# TestHBridge.net
KiCad netlist of a schematic drawn in Altium Designer
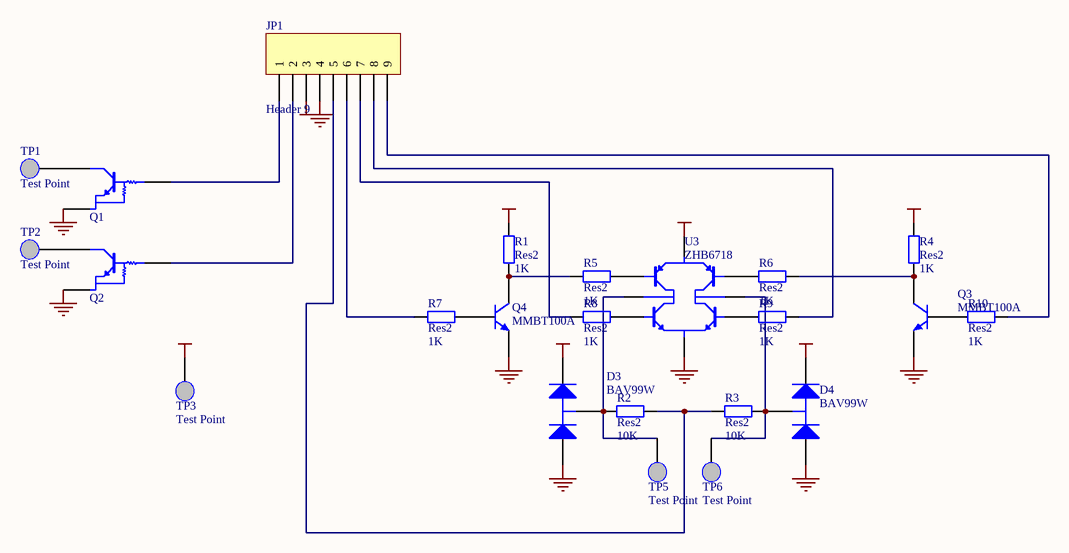
[diagram p0: TestHBridge.SchDoc]

(export (version "E")
  (design (tool "Eeschema 10.0.6"))
  (components
    (comp (ref "D3")
      (value "BAV99W")
      (footprint "SOT-323")
      (description "Silicon Switching Diode Array for High-Speed Switching")
      (fields (field (name "PUBLISHER") "Altium Limited"))
      (libsource (lib "Infineon Discrete Diode") (part "BAV99W"))
    )
    (comp (ref "D4")
      (value "BAV99W")
      (footprint "SOT-323")
      (description "Silicon Switching Diode Array for High-Speed Switching")
      (fields (field (name "PUBLISHER") "Altium Limited"))
      (libsource (lib "Infineon Discrete Diode") (part "BAV99W"))
    )
    (comp (ref "JP1")
      (value "Header 9")
      (footprint "HDR1X9")
      (description "Header, 9-Pin")
      (fields (field (name "PUBLISHER") "Altium Limited"))
      (libsource (lib "Miscellaneous Connectors") (part "Header 9"))
    )
    (comp (ref "Q1")
      (value "UN2212")
      (footprint "SO-G3")
      (description "Bias Resistor Transistor")
      (libsource (lib "Custom") (part "UN2212"))
    )
    (comp (ref "Q2")
      (value "UN2212")
      (footprint "SO-G3")
      (description "Bias Resistor Transistor")
      (libsource (lib "Custom") (part "UN2212"))
    )
    (comp (ref "Q3")
      (value "MMBT100A")
      (footprint "SO-G3")
      (description "General Purpose Amplifier NPN Silicon")
      (fields (field (name "PUBLISHER") "Altium Limited"))
      (libsource (lib "Custom") (part "MMBT100A"))
    )
    (comp (ref "Q4")
      (value "MMBT100A")
      (footprint "SO-G3")
      (description "General Purpose Amplifier NPN Silicon")
      (fields (field (name "PUBLISHER") "Altium Limited"))
      (libsource (lib "Custom") (part "MMBT100A"))
    )
    (comp (ref "R1")
      (value "Res2")
      (footprint "CC2012-0805")
      (description "Resistor")
      (fields (field (name "ALTIUM_VALUE") "1K") (field (name "PUBLISHER") "Altium Limited"))
      (libsource (lib "Miscellaneous Devices") (part "Res2"))
    )
    (comp (ref "R2")
      (value "Res2")
      (footprint "CC2012-0805")
      (description "Resistor")
      (fields (field (name "ALTIUM_VALUE") "10K") (field (name "PUBLISHER") "Altium Limited"))
      (libsource (lib "Miscellaneous Devices") (part "Res2"))
    )
    (comp (ref "R3")
      (value "Res2")
      (footprint "CC2012-0805")
      (description "Resistor")
      (fields (field (name "ALTIUM_VALUE") "10K") (field (name "PUBLISHER") "Altium Limited"))
      (libsource (lib "Miscellaneous Devices") (part "Res2"))
    )
    (comp (ref "R4")
      (value "Res2")
      (footprint "CC2012-0805")
      (description "Resistor")
      (fields (field (name "ALTIUM_VALUE") "1K") (field (name "PUBLISHER") "Altium Limited"))
      (libsource (lib "") (part "Res2_2"))
    )
    (comp (ref "R5")
      (value "Res2")
      (footprint "CC2012-0805")
      (description "Resistor")
      (fields (field (name "ALTIUM_VALUE") "1K") (field (name "PUBLISHER") "Altium Limited"))
      (libsource (lib "Miscellaneous Devices") (part "Res2"))
    )
    (comp (ref "R6")
      (value "Res2")
      (footprint "CC2012-0805")
      (description "Resistor")
      (fields (field (name "ALTIUM_VALUE") "1K") (field (name "PUBLISHER") "Altium Limited"))
      (libsource (lib "Miscellaneous Devices") (part "Res2"))
    )
    (comp (ref "R7")
      (value "Res2")
      (footprint "CC2012-0805")
      (description "Resistor")
      (fields (field (name "ALTIUM_VALUE") "1K") (field (name "PUBLISHER") "Altium Limited"))
      (libsource (lib "") (part "Res2_1"))
    )
    (comp (ref "R8")
      (value "Res2")
      (footprint "CC2012-0805")
      (description "Resistor")
      (fields (field (name "ALTIUM_VALUE") "1K") (field (name "PUBLISHER") "Altium Limited"))
      (libsource (lib "Miscellaneous Devices") (part "Res2"))
    )
    (comp (ref "R9")
      (value "Res2")
      (footprint "CC2012-0805")
      (description "Resistor")
      (fields (field (name "ALTIUM_VALUE") "1K") (field (name "PUBLISHER") "Altium Limited"))
      (libsource (lib "Miscellaneous Devices") (part "Res2"))
    )
    (comp (ref "R10")
      (value "Res2")
      (footprint "CC2012-0805")
      (description "Resistor")
      (fields (field (name "ALTIUM_VALUE") "1K") (field (name "PUBLISHER") "Altium Limited"))
      (libsource (lib "Miscellaneous Devices") (part "Res2"))
    )
    (comp (ref "TP1")
      (value "Test Point")
      (footprint "TestPoint")
      (libsource (lib "Custom") (part "TestPoint"))
    )
    (comp (ref "TP2")
      (value "Test Point")
      (footprint "TestPoint")
      (libsource (lib "Custom") (part "TestPoint"))
    )
    (comp (ref "TP3")
      (value "Test Point")
      (footprint "TestPoint")
      (libsource (lib "Custom") (part "TestPoint"))
    )
    (comp (ref "TP5")
      (value "Test Point")
      (footprint "TestPoint")
      (libsource (lib "Custom") (part "TestPoint"))
    )
    (comp (ref "TP6")
      (value "Test Point")
      (footprint "TestPoint")
      (libsource (lib "Custom") (part "TestPoint"))
    )
    (comp (ref "U3") (value "ZHB6718") (footprint "SOT223-8") (libsource (lib "Custom") (part "ZHB6718")))
  )
  (nets
    (net (code "1") (name "GND") (class "Default")
      (node (ref "D3") (pin "1") (pinfunction "A_1") (pintype "passive"))
      (node (ref "D4") (pin "1") (pinfunction "A_1") (pintype "passive"))
      (node (ref "JP1") (pin "4") (pinfunction "4_4") (pintype "passive"))
      (node (ref "Q1") (pin "2") (pinfunction "E_2") (pintype "passive"))
      (node (ref "Q2") (pin "2") (pinfunction "E_2") (pintype "passive"))
      (node (ref "Q3") (pin "2") (pinfunction "E_2") (pintype "passive"))
      (node (ref "Q4") (pin "2") (pinfunction "E_2") (pintype "passive"))
      (node (ref "U3") (pin "2") (pinfunction "e2,e3_2") (pintype "passive"))
    )
    (net (code "2") (name "Net-(D3-C)") (class "Default")
      (node (ref "D3") (pin "3") (pinfunction "C_3") (pintype "passive"))
      (node (ref "R2") (pin "1") (pinfunction "1_1") (pintype "passive"))
      (node (ref "TP5") (pin "1") (pintype "passive"))
      (node (ref "U3") (pin "5") (pinfunction "c1,c2_5") (pintype "passive"))
    )
    (net (code "3") (name "Net-(D4-C)") (class "Default")
      (node (ref "D4") (pin "3") (pinfunction "C_3") (pintype "passive"))
      (node (ref "R3") (pin "2") (pinfunction "2_2") (pintype "passive"))
      (node (ref "TP6") (pin "1") (pintype "passive"))
      (node (ref "U3") (pin "7") (pinfunction "c3,c4_7") (pintype "passive"))
    )
    (net (code "4") (name "Net-(JP1-Pad5)") (class "Default")
      (node (ref "JP1") (pin "5") (pinfunction "5_5") (pintype "passive"))
      (node (ref "R2") (pin "2") (pinfunction "2_2") (pintype "passive"))
      (node (ref "R3") (pin "1") (pinfunction "1_1") (pintype "passive"))
    )
    (net (code "5") (name "Net-(JP1-Pad6)") (class "Default")
      (node (ref "JP1") (pin "6") (pinfunction "6_6") (pintype "passive"))
      (node (ref "R7") (pin "2") (pinfunction "2_2") (pintype "passive"))
    )
    (net (code "6") (name "Net-(JP1-Pad7)") (class "Default")
      (node (ref "JP1") (pin "7") (pinfunction "7_7") (pintype "passive"))
      (node (ref "R8") (pin "1") (pinfunction "1_1") (pintype "passive"))
    )
    (net (code "7") (name "Net-(JP1-Pad8)") (class "Default")
      (node (ref "JP1") (pin "8") (pinfunction "8_8") (pintype "passive"))
      (node (ref "R9") (pin "2") (pinfunction "2_2") (pintype "passive"))
    )
    (net (code "8") (name "Net-(JP1-Pad9)") (class "Default")
      (node (ref "JP1") (pin "9") (pinfunction "9_9") (pintype "passive"))
      (node (ref "R10") (pin "2") (pinfunction "2_2") (pintype "passive"))
    )
    (net (code "9") (name "Net-(Q1-B)") (class "Default")
      (node (ref "JP1") (pin "1") (pinfunction "1_1") (pintype "passive"))
      (node (ref "Q1") (pin "1") (pinfunction "B_1") (pintype "passive"))
    )
    (net (code "10") (name "Net-(Q1-C)") (class "Default")
      (node (ref "Q1") (pin "3") (pinfunction "C_3") (pintype "passive"))
      (node (ref "TP1") (pin "1") (pintype "passive"))
    )
    (net (code "11") (name "Net-(Q2-B)") (class "Default")
      (node (ref "JP1") (pin "2") (pinfunction "2_2") (pintype "passive"))
      (node (ref "Q2") (pin "1") (pinfunction "B_1") (pintype "passive"))
    )
    (net (code "12") (name "Net-(Q2-C)") (class "Default")
      (node (ref "Q2") (pin "3") (pinfunction "C_3") (pintype "passive"))
      (node (ref "TP2") (pin "1") (pintype "passive"))
    )
    (net (code "13") (name "Net-(Q3-B)") (class "Default")
      (node (ref "Q3") (pin "1") (pinfunction "B_1") (pintype "passive"))
      (node (ref "R10") (pin "1") (pinfunction "1_1") (pintype "passive"))
    )
    (net (code "14") (name "Net-(Q3-C)") (class "Default")
      (node (ref "Q3") (pin "3") (pinfunction "C_3") (pintype "passive"))
      (node (ref "R4") (pin "1") (pinfunction "1_1") (pintype "passive"))
      (node (ref "R6") (pin "2") (pinfunction "2_2") (pintype "passive"))
    )
    (net (code "15") (name "Net-(Q4-B)") (class "Default")
      (node (ref "Q4") (pin "1") (pinfunction "B_1") (pintype "passive"))
      (node (ref "R7") (pin "1") (pinfunction "1_1") (pintype "passive"))
    )
    (net (code "16") (name "Net-(Q4-C)") (class "Default")
      (node (ref "Q4") (pin "3") (pinfunction "C_3") (pintype "passive"))
      (node (ref "R1") (pin "1") (pinfunction "1_1") (pintype "passive"))
      (node (ref "R5") (pin "1") (pinfunction "1_1") (pintype "passive"))
    )
    (net (code "17") (name "Net-(U3-b1)") (class "Default")
      (node (ref "R5") (pin "2") (pinfunction "2_2") (pintype "passive"))
      (node (ref "U3") (pin "4") (pinfunction "b1_4") (pintype "passive"))
    )
    (net (code "18") (name "Net-(U3-b2)") (class "Default")
      (node (ref "R8") (pin "2") (pinfunction "2_2") (pintype "passive"))
      (node (ref "U3") (pin "3") (pinfunction "b2_3") (pintype "passive"))
    )
    (net (code "19") (name "Net-(U3-b3)") (class "Default")
      (node (ref "R9") (pin "1") (pinfunction "1_1") (pintype "passive"))
      (node (ref "U3") (pin "1") (pinfunction "b3_1") (pintype "passive"))
    )
    (net (code "20") (name "Net-(U3-b4)") (class "Default")
      (node (ref "R6") (pin "1") (pinfunction "1_1") (pintype "passive"))
      (node (ref "U3") (pin "8") (pinfunction "b4_8") (pintype "passive"))
    )
    (net (code "21") (name "Vdd") (class "Default")
      (node (ref "D3") (pin "2") (pinfunction "K_2") (pintype "passive"))
      (node (ref "D4") (pin "2") (pinfunction "K_2") (pintype "passive"))
      (node (ref "JP1") (pin "3") (pinfunction "3_3") (pintype "passive"))
      (node (ref "R1") (pin "2") (pinfunction "2_2") (pintype "passive"))
      (node (ref "R4") (pin "2") (pinfunction "2_2") (pintype "passive"))
      (node (ref "TP3") (pin "1") (pintype "passive"))
      (node (ref "U3") (pin "6") (pinfunction "e1,e4_6") (pintype "passive"))
    )
  )
)
